# PhasedArrayTransmittor.net
KiCad netlist of a schematic drawn in EAGLE
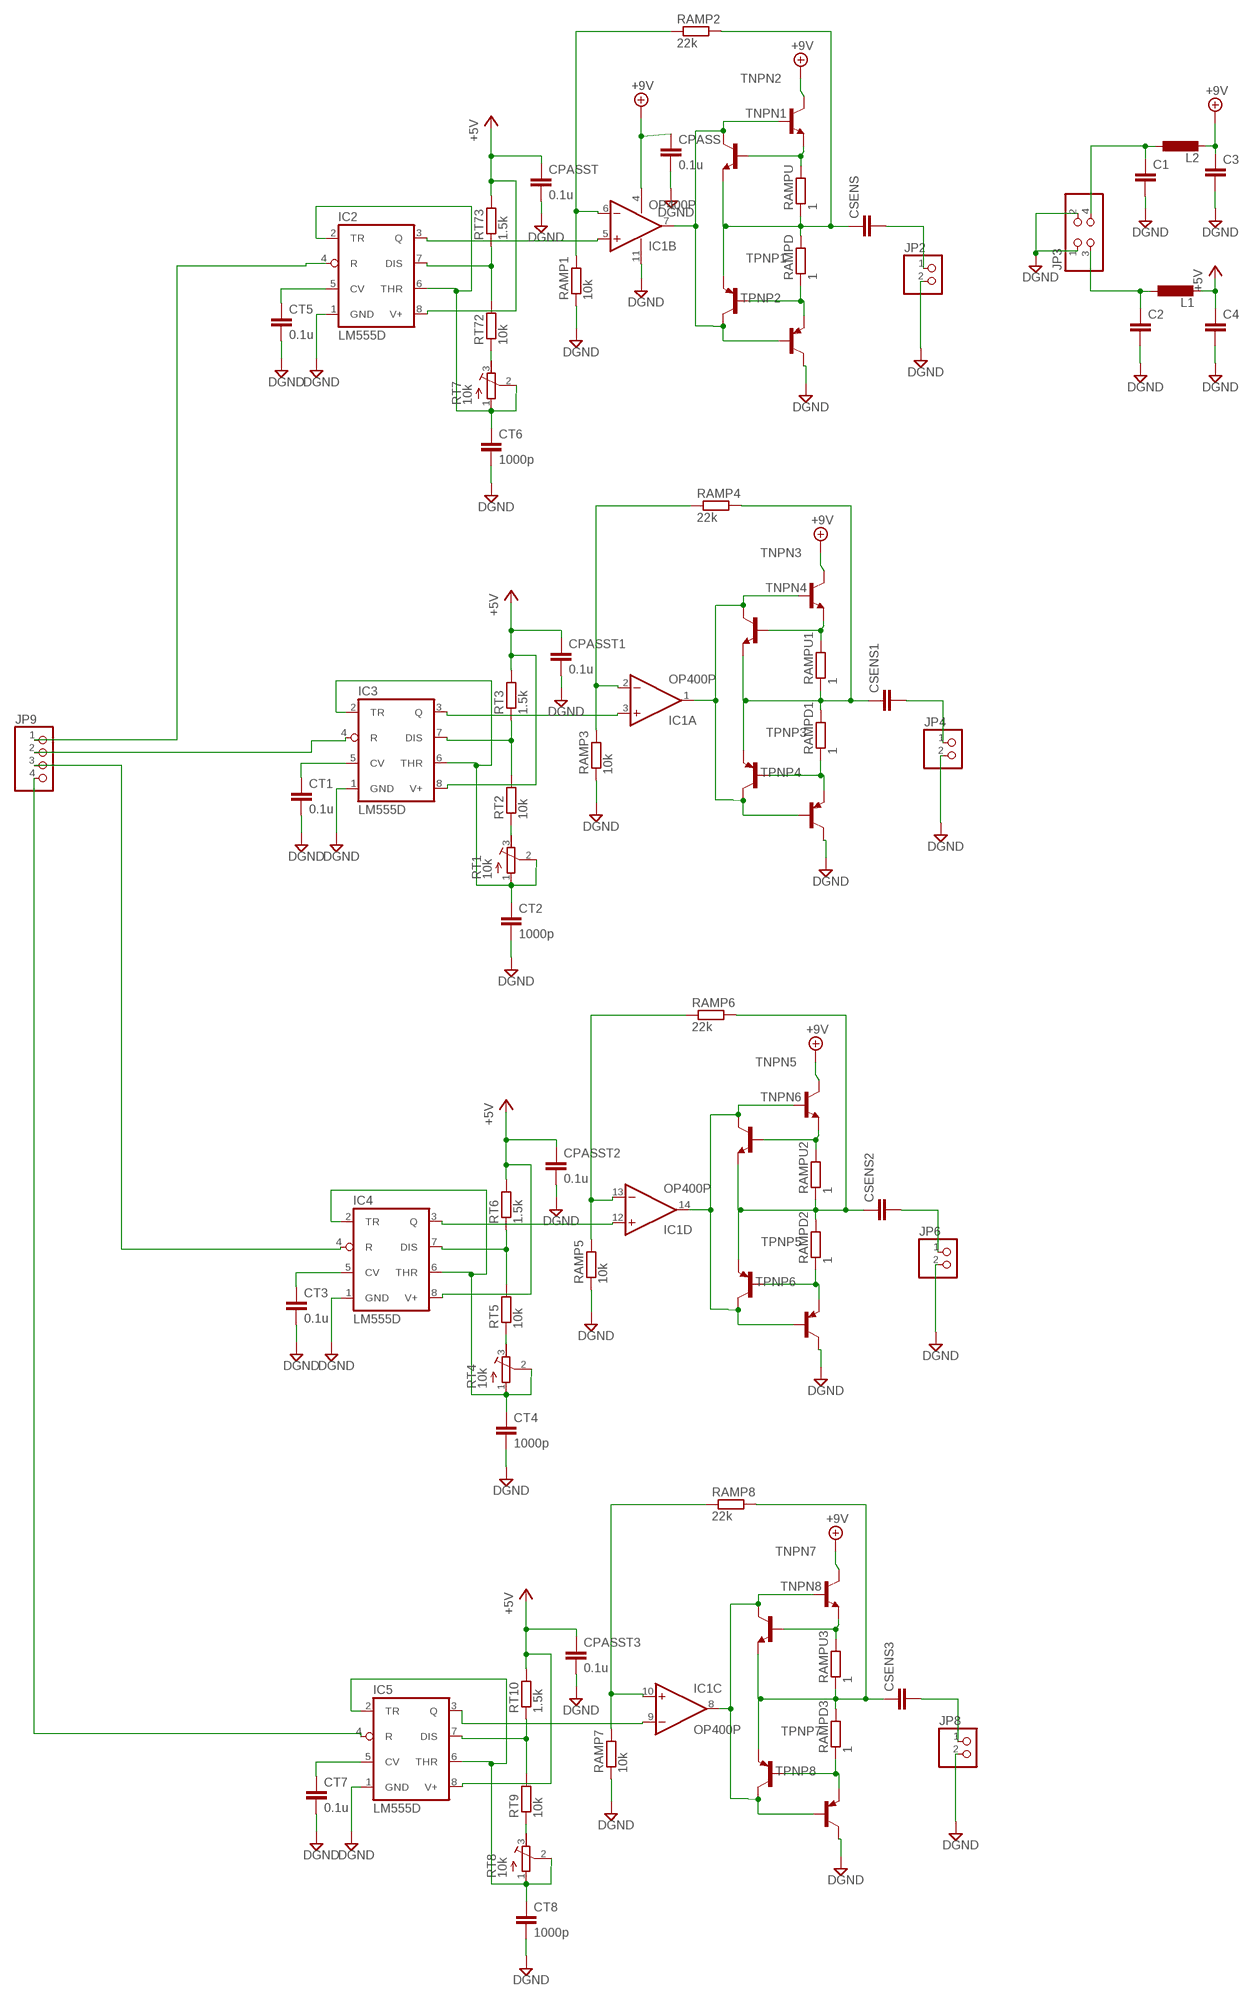
[diagram p0: schematic, sheet 1]

(export (version "E")
  (design (tool "Eeschema 10.0.6"))
  (components
    (comp (ref "C1")
      (value "C-EU025-024X044")
      (footprint "eagle-import:C025-024X044")
      (libsource (lib "eagle-import") (part "C-EU025-024X044"))
    )
    (comp (ref "C2")
      (value "C-EU025-024X044")
      (footprint "eagle-import:C025-024X044")
      (libsource (lib "eagle-import") (part "C-EU025-024X044"))
    )
    (comp (ref "C3")
      (value "C-EU025-024X044")
      (footprint "eagle-import:C025-024X044")
      (libsource (lib "eagle-import") (part "C-EU025-024X044"))
    )
    (comp (ref "C4")
      (value "C-EU025-024X044")
      (footprint "eagle-import:C025-024X044")
      (libsource (lib "eagle-import") (part "C-EU025-024X044"))
    )
    (comp (ref "CPASS")
      (value "0.1u")
      (footprint "eagle-import:C0603K")
      (libsource (lib "eagle-import") (part "C-EUC0603K"))
    )
    (comp (ref "CPASST")
      (value "0.1u")
      (footprint "eagle-import:C025-024X044")
      (libsource (lib "eagle-import") (part "C-EU025-024X044"))
    )
    (comp (ref "CPASST1")
      (value "0.1u")
      (footprint "eagle-import:C025-024X044")
      (libsource (lib "eagle-import") (part "C-EU025-024X044"))
    )
    (comp (ref "CPASST2")
      (value "0.1u")
      (footprint "eagle-import:C025-024X044")
      (libsource (lib "eagle-import") (part "C-EU025-024X044"))
    )
    (comp (ref "CPASST3")
      (value "0.1u")
      (footprint "eagle-import:C025-024X044")
      (libsource (lib "eagle-import") (part "C-EU025-024X044"))
    )
    (comp (ref "CSENS")
      (value "C-EUC0603K")
      (footprint "eagle-import:C0603K")
      (libsource (lib "eagle-import") (part "C-EUC0603K"))
    )
    (comp (ref "CSENS1")
      (value "C-EUC0603K")
      (footprint "eagle-import:C0603K")
      (libsource (lib "eagle-import") (part "C-EUC0603K"))
    )
    (comp (ref "CSENS2")
      (value "C-EUC0603K")
      (footprint "eagle-import:C0603K")
      (libsource (lib "eagle-import") (part "C-EUC0603K"))
    )
    (comp (ref "CSENS3")
      (value "C-EUC0603K")
      (footprint "eagle-import:C0603K")
      (libsource (lib "eagle-import") (part "C-EUC0603K"))
    )
    (comp (ref "CT1")
      (value "0.1u")
      (footprint "eagle-import:C025-024X044")
      (libsource (lib "eagle-import") (part "C-EU025-024X044"))
    )
    (comp (ref "CT2")
      (value "1000p")
      (footprint "eagle-import:C025-024X044")
      (libsource (lib "eagle-import") (part "C-EU025-024X044"))
    )
    (comp (ref "CT3")
      (value "0.1u")
      (footprint "eagle-import:C025-024X044")
      (libsource (lib "eagle-import") (part "C-EU025-024X044"))
    )
    (comp (ref "CT4")
      (value "1000p")
      (footprint "eagle-import:C025-024X044")
      (libsource (lib "eagle-import") (part "C-EU025-024X044"))
    )
    (comp (ref "CT5")
      (value "0.1u")
      (footprint "eagle-import:C025-024X044")
      (libsource (lib "eagle-import") (part "C-EU025-024X044"))
    )
    (comp (ref "CT6")
      (value "1000p")
      (footprint "eagle-import:C025-024X044")
      (libsource (lib "eagle-import") (part "C-EU025-024X044"))
    )
    (comp (ref "CT7")
      (value "0.1u")
      (footprint "eagle-import:C025-024X044")
      (libsource (lib "eagle-import") (part "C-EU025-024X044"))
    )
    (comp (ref "CT8")
      (value "1000p")
      (footprint "eagle-import:C025-024X044")
      (libsource (lib "eagle-import") (part "C-EU025-024X044"))
    )
    (comp (ref "IC1")
      (value "OP400P")
      (footprint "eagle-import:DIL14")
      (libsource (lib "eagle-import") (part "OP400P"))
    )
    (comp (ref "IC2")
      (value "LM555D")
      (footprint "eagle-import:SO08")
      (libsource (lib "eagle-import") (part "555DLM"))
    )
    (comp (ref "IC3")
      (value "LM555D")
      (footprint "eagle-import:SO08")
      (libsource (lib "eagle-import") (part "555DLM"))
    )
    (comp (ref "IC4")
      (value "LM555D")
      (footprint "eagle-import:SO08")
      (libsource (lib "eagle-import") (part "555DLM"))
    )
    (comp (ref "IC5")
      (value "LM555D")
      (footprint "eagle-import:SO08")
      (libsource (lib "eagle-import") (part "555DLM"))
    )
    (comp (ref "JP2")
      (value "PINHD-1X2")
      (footprint "eagle-import:1X02")
      (libsource (lib "eagle-import") (part "PINHD-1X2"))
    )
    (comp (ref "JP3")
      (value "PINHD-2X2")
      (footprint "eagle-import:2X02")
      (libsource (lib "eagle-import") (part "PINHD-2X2"))
    )
    (comp (ref "JP4")
      (value "PINHD-1X2")
      (footprint "eagle-import:1X02")
      (libsource (lib "eagle-import") (part "PINHD-1X2"))
    )
    (comp (ref "JP6")
      (value "PINHD-1X2")
      (footprint "eagle-import:1X02")
      (libsource (lib "eagle-import") (part "PINHD-1X2"))
    )
    (comp (ref "JP8")
      (value "PINHD-1X2")
      (footprint "eagle-import:1X02")
      (libsource (lib "eagle-import") (part "PINHD-1X2"))
    )
    (comp (ref "JP9")
      (value "PINHD-1X4")
      (footprint "eagle-import:1X04")
      (libsource (lib "eagle-import") (part "PINHD-1X4"))
    )
    (comp (ref "L1")
      (value "L-EU0207/7")
      (footprint "eagle-import:0207_7")
      (libsource (lib "eagle-import") (part "L-EU0207/7"))
    )
    (comp (ref "L2")
      (value "L-EU0207/7")
      (footprint "eagle-import:0207_7")
      (libsource (lib "eagle-import") (part "L-EU0207/7"))
    )
    (comp (ref "RAMP1")
      (value "10k")
      (footprint "eagle-import:R0603")
      (libsource (lib "eagle-import") (part "R-EU_R0603"))
    )
    (comp (ref "RAMP2")
      (value "22k")
      (footprint "eagle-import:R0603")
      (libsource (lib "eagle-import") (part "R-EU_R0603"))
    )
    (comp (ref "RAMP3")
      (value "10k")
      (footprint "eagle-import:R0603")
      (libsource (lib "eagle-import") (part "R-EU_R0603"))
    )
    (comp (ref "RAMP4")
      (value "22k")
      (footprint "eagle-import:R0603")
      (libsource (lib "eagle-import") (part "R-EU_R0603"))
    )
    (comp (ref "RAMP5")
      (value "10k")
      (footprint "eagle-import:R0603")
      (libsource (lib "eagle-import") (part "R-EU_R0603"))
    )
    (comp (ref "RAMP6")
      (value "22k")
      (footprint "eagle-import:R0603")
      (libsource (lib "eagle-import") (part "R-EU_R0603"))
    )
    (comp (ref "RAMP7")
      (value "10k")
      (footprint "eagle-import:R0603")
      (libsource (lib "eagle-import") (part "R-EU_R0603"))
    )
    (comp (ref "RAMP8")
      (value "22k")
      (footprint "eagle-import:R0603")
      (libsource (lib "eagle-import") (part "R-EU_R0603"))
    )
    (comp (ref "RAMPD")
      (value "1")
      (footprint "eagle-import:R0603")
      (libsource (lib "eagle-import") (part "R-EU_R0603"))
    )
    (comp (ref "RAMPD1")
      (value "1")
      (footprint "eagle-import:R0603")
      (libsource (lib "eagle-import") (part "R-EU_R0603"))
    )
    (comp (ref "RAMPD2")
      (value "1")
      (footprint "eagle-import:R0603")
      (libsource (lib "eagle-import") (part "R-EU_R0603"))
    )
    (comp (ref "RAMPD3")
      (value "1")
      (footprint "eagle-import:R0603")
      (libsource (lib "eagle-import") (part "R-EU_R0603"))
    )
    (comp (ref "RAMPU")
      (value "1")
      (footprint "eagle-import:R0603")
      (libsource (lib "eagle-import") (part "R-EU_R0603"))
    )
    (comp (ref "RAMPU1")
      (value "1")
      (footprint "eagle-import:R0603")
      (libsource (lib "eagle-import") (part "R-EU_R0603"))
    )
    (comp (ref "RAMPU2")
      (value "1")
      (footprint "eagle-import:R0603")
      (libsource (lib "eagle-import") (part "R-EU_R0603"))
    )
    (comp (ref "RAMPU3")
      (value "1")
      (footprint "eagle-import:R0603")
      (libsource (lib "eagle-import") (part "R-EU_R0603"))
    )
    (comp (ref "RT1")
      (value "10k")
      (footprint "eagle-import:RTRIM74W")
      (libsource (lib "eagle-import") (part "R-TRIMM74W"))
    )
    (comp (ref "RT2")
      (value "10k")
      (footprint "eagle-import:R0603")
      (libsource (lib "eagle-import") (part "R-EU_R0603"))
    )
    (comp (ref "RT3")
      (value "1.5k")
      (footprint "eagle-import:R0603")
      (libsource (lib "eagle-import") (part "R-EU_R0603"))
    )
    (comp (ref "RT4")
      (value "10k")
      (footprint "eagle-import:RTRIM74W")
      (libsource (lib "eagle-import") (part "R-TRIMM74W"))
    )
    (comp (ref "RT5")
      (value "10k")
      (footprint "eagle-import:R0603")
      (libsource (lib "eagle-import") (part "R-EU_R0603"))
    )
    (comp (ref "RT6")
      (value "1.5k")
      (footprint "eagle-import:R0603")
      (libsource (lib "eagle-import") (part "R-EU_R0603"))
    )
    (comp (ref "RT7")
      (value "10k")
      (footprint "eagle-import:RTRIM74W")
      (libsource (lib "eagle-import") (part "R-TRIMM74W"))
    )
    (comp (ref "RT8")
      (value "10k")
      (footprint "eagle-import:RTRIM74W")
      (libsource (lib "eagle-import") (part "R-TRIMM74W"))
    )
    (comp (ref "RT9")
      (value "10k")
      (footprint "eagle-import:R0603")
      (libsource (lib "eagle-import") (part "R-EU_R0603"))
    )
    (comp (ref "RT10")
      (value "1.5k")
      (footprint "eagle-import:R0603")
      (libsource (lib "eagle-import") (part "R-EU_R0603"))
    )
    (comp (ref "RT72")
      (value "10k")
      (footprint "eagle-import:R0603")
      (libsource (lib "eagle-import") (part "R-EU_R0603"))
    )
    (comp (ref "RT73")
      (value "1.5k")
      (footprint "eagle-import:R0603")
      (libsource (lib "eagle-import") (part "R-EU_R0603"))
    )
    (comp (ref "TNPN1")
      (value "BC817-16-NPN-SOT23-BEC")
      (footprint "eagle-import:SOT23-BEC")
      (libsource (lib "eagle-import") (part "-NPN-SOT23-BECBC817-16"))
    )
    (comp (ref "TNPN2")
      (value "BC817-16-NPN-SOT23-BEC")
      (footprint "eagle-import:SOT23-BEC")
      (libsource (lib "eagle-import") (part "-NPN-SOT23-BECBC817-16"))
    )
    (comp (ref "TNPN3")
      (value "BC817-16-NPN-SOT23-BEC")
      (footprint "eagle-import:SOT23-BEC")
      (libsource (lib "eagle-import") (part "-NPN-SOT23-BECBC817-16"))
    )
    (comp (ref "TNPN4")
      (value "BC817-16-NPN-SOT23-BEC")
      (footprint "eagle-import:SOT23-BEC")
      (libsource (lib "eagle-import") (part "-NPN-SOT23-BECBC817-16"))
    )
    (comp (ref "TNPN5")
      (value "BC817-16-NPN-SOT23-BEC")
      (footprint "eagle-import:SOT23-BEC")
      (libsource (lib "eagle-import") (part "-NPN-SOT23-BECBC817-16"))
    )
    (comp (ref "TNPN6")
      (value "BC817-16-NPN-SOT23-BEC")
      (footprint "eagle-import:SOT23-BEC")
      (libsource (lib "eagle-import") (part "-NPN-SOT23-BECBC817-16"))
    )
    (comp (ref "TNPN7")
      (value "BC817-16-NPN-SOT23-BEC")
      (footprint "eagle-import:SOT23-BEC")
      (libsource (lib "eagle-import") (part "-NPN-SOT23-BECBC817-16"))
    )
    (comp (ref "TNPN8")
      (value "BC817-16-NPN-SOT23-BEC")
      (footprint "eagle-import:SOT23-BEC")
      (libsource (lib "eagle-import") (part "-NPN-SOT23-BECBC817-16"))
    )
    (comp (ref "TPNP1")
      (value "BC807-16-PNP-SOT23-BEC")
      (footprint "eagle-import:SOT23-BEC")
      (libsource (lib "eagle-import") (part "-PNP-SOT23-BECBC807-16"))
    )
    (comp (ref "TPNP2")
      (value "BC807-16-PNP-SOT23-BEC")
      (footprint "eagle-import:SOT23-BEC")
      (libsource (lib "eagle-import") (part "-PNP-SOT23-BECBC807-16"))
    )
    (comp (ref "TPNP3")
      (value "BC807-16-PNP-SOT23-BEC")
      (footprint "eagle-import:SOT23-BEC")
      (libsource (lib "eagle-import") (part "-PNP-SOT23-BECBC807-16"))
    )
    (comp (ref "TPNP4")
      (value "BC807-16-PNP-SOT23-BEC")
      (footprint "eagle-import:SOT23-BEC")
      (libsource (lib "eagle-import") (part "-PNP-SOT23-BECBC807-16"))
    )
    (comp (ref "TPNP5")
      (value "BC807-16-PNP-SOT23-BEC")
      (footprint "eagle-import:SOT23-BEC")
      (libsource (lib "eagle-import") (part "-PNP-SOT23-BECBC807-16"))
    )
    (comp (ref "TPNP6")
      (value "BC807-16-PNP-SOT23-BEC")
      (footprint "eagle-import:SOT23-BEC")
      (libsource (lib "eagle-import") (part "-PNP-SOT23-BECBC807-16"))
    )
    (comp (ref "TPNP7")
      (value "BC807-16-PNP-SOT23-BEC")
      (footprint "eagle-import:SOT23-BEC")
      (libsource (lib "eagle-import") (part "-PNP-SOT23-BECBC807-16"))
    )
    (comp (ref "TPNP8")
      (value "BC807-16-PNP-SOT23-BEC")
      (footprint "eagle-import:SOT23-BEC")
      (libsource (lib "eagle-import") (part "-PNP-SOT23-BECBC807-16"))
    )
  )
  (nets
    (net (code "1") (name "+5V") (class "Default")
      (node (ref "C4") (pin "1") (pinfunction "1_1") (pintype "passive"))
      (node (ref "CPASST") (pin "1") (pinfunction "1_1") (pintype "passive"))
      (node (ref "CPASST1") (pin "1") (pinfunction "1_1") (pintype "passive"))
      (node (ref "CPASST2") (pin "1") (pinfunction "1_1") (pintype "passive"))
      (node (ref "CPASST3") (pin "1") (pinfunction "1_1") (pintype "passive"))
      (node (ref "IC2") (pin "8") (pinfunction "V+_8") (pintype "power_in"))
      (node (ref "IC3") (pin "8") (pinfunction "V+_8") (pintype "power_in"))
      (node (ref "IC4") (pin "8") (pinfunction "V+_8") (pintype "power_in"))
      (node (ref "IC5") (pin "8") (pinfunction "V+_8") (pintype "power_in"))
      (node (ref "L1") (pin "2") (pinfunction "2_2") (pintype "passive"))
      (node (ref "RT10") (pin "2") (pinfunction "2_2") (pintype "passive"))
      (node (ref "RT3") (pin "2") (pinfunction "2_2") (pintype "passive"))
      (node (ref "RT6") (pin "2") (pinfunction "2_2") (pintype "passive"))
      (node (ref "RT73") (pin "2") (pinfunction "2_2") (pintype "passive"))
    )
    (net (code "2") (name "+9V") (class "Default")
      (node (ref "C3") (pin "1") (pinfunction "1_1") (pintype "passive"))
      (node (ref "CPASS") (pin "1") (pinfunction "1_1") (pintype "passive"))
      (node (ref "IC1") (pin "4") (pinfunction "V+_4") (pintype "power_in"))
      (node (ref "L2") (pin "2") (pinfunction "2_2") (pintype "passive"))
      (node (ref "TNPN2") (pin "C") (pinfunction "C_C") (pintype "passive"))
      (node (ref "TNPN3") (pin "C") (pinfunction "C_C") (pintype "passive"))
      (node (ref "TNPN5") (pin "C") (pinfunction "C_C") (pintype "passive"))
      (node (ref "TNPN7") (pin "C") (pinfunction "C_C") (pintype "passive"))
    )
    (net (code "3") (name "DGND") (class "Default")
      (node (ref "C1") (pin "2") (pinfunction "2_2") (pintype "passive"))
      (node (ref "C2") (pin "2") (pinfunction "2_2") (pintype "passive"))
      (node (ref "C3") (pin "2") (pinfunction "2_2") (pintype "passive"))
      (node (ref "C4") (pin "2") (pinfunction "2_2") (pintype "passive"))
      (node (ref "CPASS") (pin "2") (pinfunction "2_2") (pintype "passive"))
      (node (ref "CPASST") (pin "2") (pinfunction "2_2") (pintype "passive"))
      (node (ref "CPASST1") (pin "2") (pinfunction "2_2") (pintype "passive"))
      (node (ref "CPASST2") (pin "2") (pinfunction "2_2") (pintype "passive"))
      (node (ref "CPASST3") (pin "2") (pinfunction "2_2") (pintype "passive"))
      (node (ref "CT1") (pin "2") (pinfunction "2_2") (pintype "passive"))
      (node (ref "CT2") (pin "2") (pinfunction "2_2") (pintype "passive"))
      (node (ref "CT3") (pin "2") (pinfunction "2_2") (pintype "passive"))
      (node (ref "CT4") (pin "2") (pinfunction "2_2") (pintype "passive"))
      (node (ref "CT5") (pin "2") (pinfunction "2_2") (pintype "passive"))
      (node (ref "CT6") (pin "2") (pinfunction "2_2") (pintype "passive"))
      (node (ref "CT7") (pin "2") (pinfunction "2_2") (pintype "passive"))
      (node (ref "CT8") (pin "2") (pinfunction "2_2") (pintype "passive"))
      (node (ref "IC1") (pin "11") (pinfunction "V-_11") (pintype "power_in"))
      (node (ref "IC2") (pin "1") (pinfunction "GND_1") (pintype "power_in"))
      (node (ref "IC3") (pin "1") (pinfunction "GND_1") (pintype "power_in"))
      (node (ref "IC4") (pin "1") (pinfunction "GND_1") (pintype "power_in"))
      (node (ref "IC5") (pin "1") (pinfunction "GND_1") (pintype "power_in"))
      (node (ref "JP2") (pin "2") (pinfunction "2_2") (pintype "passive"))
      (node (ref "JP3") (pin "1") (pinfunction "1_1") (pintype "passive"))
      (node (ref "JP3") (pin "2") (pinfunction "2_2") (pintype "passive"))
      (node (ref "JP4") (pin "2") (pinfunction "2_2") (pintype "passive"))
      (node (ref "JP6") (pin "2") (pinfunction "2_2") (pintype "passive"))
      (node (ref "JP8") (pin "2") (pinfunction "2_2") (pintype "passive"))
      (node (ref "RAMP1") (pin "1") (pinfunction "1_1") (pintype "passive"))
      (node (ref "RAMP3") (pin "1") (pinfunction "1_1") (pintype "passive"))
      (node (ref "RAMP5") (pin "1") (pinfunction "1_1") (pintype "passive"))
      (node (ref "RAMP7") (pin "1") (pinfunction "1_1") (pintype "passive"))
      (node (ref "TPNP2") (pin "C") (pinfunction "C_C") (pintype "passive"))
      (node (ref "TPNP4") (pin "C") (pinfunction "C_C") (pintype "passive"))
      (node (ref "TPNP6") (pin "C") (pinfunction "C_C") (pintype "passive"))
      (node (ref "TPNP8") (pin "C") (pinfunction "C_C") (pintype "passive"))
    )
    (net (code "4") (name "Net-(C1-Pad1)") (class "Default")
      (node (ref "C1") (pin "1") (pinfunction "1_1") (pintype "passive"))
      (node (ref "JP3") (pin "4") (pinfunction "4_4") (pintype "passive"))
      (node (ref "L2") (pin "1") (pinfunction "1_1") (pintype "passive"))
    )
    (net (code "5") (name "Net-(C2-Pad1)") (class "Default")
      (node (ref "C2") (pin "1") (pinfunction "1_1") (pintype "passive"))
      (node (ref "JP3") (pin "3") (pinfunction "3_3") (pintype "passive"))
      (node (ref "L1") (pin "1") (pinfunction "1_1") (pintype "passive"))
    )
    (net (code "6") (name "Net-(CSENS-Pad1)") (class "Default")
      (node (ref "CSENS") (pin "1") (pinfunction "1_1") (pintype "passive"))
      (node (ref "RAMP2") (pin "2") (pinfunction "2_2") (pintype "passive"))
      (node (ref "RAMPD") (pin "2") (pinfunction "2_2") (pintype "passive"))
      (node (ref "RAMPU") (pin "1") (pinfunction "1_1") (pintype "passive"))
      (node (ref "TNPN1") (pin "E") (pinfunction "E_E") (pintype "passive"))
      (node (ref "TPNP1") (pin "E") (pinfunction "E_E") (pintype "passive"))
    )
    (net (code "7") (name "Net-(CSENS-Pad2)") (class "Default")
      (node (ref "CSENS") (pin "2") (pinfunction "2_2") (pintype "passive"))
      (node (ref "JP2") (pin "1") (pinfunction "1_1") (pintype "passive"))
    )
    (net (code "8") (name "Net-(CSENS1-Pad1)") (class "Default")
      (node (ref "CSENS1") (pin "1") (pinfunction "1_1") (pintype "passive"))
      (node (ref "RAMP4") (pin "2") (pinfunction "2_2") (pintype "passive"))
      (node (ref "RAMPD1") (pin "2") (pinfunction "2_2") (pintype "passive"))
      (node (ref "RAMPU1") (pin "1") (pinfunction "1_1") (pintype "passive"))
      (node (ref "TNPN4") (pin "E") (pinfunction "E_E") (pintype "passive"))
      (node (ref "TPNP3") (pin "E") (pinfunction "E_E") (pintype "passive"))
    )
    (net (code "9") (name "Net-(CSENS1-Pad2)") (class "Default")
      (node (ref "CSENS1") (pin "2") (pinfunction "2_2") (pintype "passive"))
      (node (ref "JP4") (pin "1") (pinfunction "1_1") (pintype "passive"))
    )
    (net (code "10") (name "Net-(CSENS2-Pad1)") (class "Default")
      (node (ref "CSENS2") (pin "1") (pinfunction "1_1") (pintype "passive"))
      (node (ref "RAMP6") (pin "2") (pinfunction "2_2") (pintype "passive"))
      (node (ref "RAMPD2") (pin "2") (pinfunction "2_2") (pintype "passive"))
      (node (ref "RAMPU2") (pin "1") (pinfunction "1_1") (pintype "passive"))
      (node (ref "TNPN6") (pin "E") (pinfunction "E_E") (pintype "passive"))
      (node (ref "TPNP5") (pin "E") (pinfunction "E_E") (pintype "passive"))
    )
    (net (code "11") (name "Net-(CSENS2-Pad2)") (class "Default")
      (node (ref "CSENS2") (pin "2") (pinfunction "2_2") (pintype "passive"))
      (node (ref "JP6") (pin "1") (pinfunction "1_1") (pintype "passive"))
    )
    (net (code "12") (name "Net-(CSENS3-Pad1)") (class "Default")
      (node (ref "CSENS3") (pin "1") (pinfunction "1_1") (pintype "passive"))
      (node (ref "RAMP8") (pin "2") (pinfunction "2_2") (pintype "passive"))
      (node (ref "RAMPD3") (pin "2") (pinfunction "2_2") (pintype "passive"))
      (node (ref "RAMPU3") (pin "1") (pinfunction "1_1") (pintype "passive"))
      (node (ref "TNPN8") (pin "E") (pinfunction "E_E") (pintype "passive"))
      (node (ref "TPNP7") (pin "E") (pinfunction "E_E") (pintype "passive"))
    )
    (net (code "13") (name "Net-(CSENS3-Pad2)") (class "Default")
      (node (ref "CSENS3") (pin "2") (pinfunction "2_2") (pintype "passive"))
      (node (ref "JP8") (pin "1") (pinfunction "1_1") (pintype "passive"))
    )
    (net (code "14") (name "Net-(IC1A-+IN)") (class "Default")
      (node (ref "IC1") (pin "3") (pinfunction "+IN_3") (pintype "input"))
      (node (ref "IC3") (pin "3") (pinfunction "Q_3") (pintype "output"))
    )
    (net (code "15") (name "Net-(IC1A--IN)") (class "Default")
      (node (ref "IC1") (pin "2") (pinfunction "-IN_2") (pintype "input"))
      (node (ref "RAMP3") (pin "2") (pinfunction "2_2") (pintype "passive"))
      (node (ref "RAMP4") (pin "1") (pinfunction "1_1") (pintype "passive"))
    )
    (net (code "16") (name "Net-(IC1A-OUT)") (class "Default")
      (node (ref "IC1") (pin "1") (pinfunction "OUT_1") (pintype "output"))
      (node (ref "TNPN3") (pin "B") (pinfunction "B_B") (pintype "passive"))
      (node (ref "TNPN4") (pin "C") (pinfunction "C_C") (pintype "passive"))
      (node (ref "TPNP3") (pin "C") (pinfunction "C_C") (pintype "passive"))
      (node (ref "TPNP4") (pin "B") (pinfunction "B_B") (pintype "passive"))
    )
    (net (code "17") (name "Net-(IC1B-+IN)") (class "Default")
      (node (ref "IC1") (pin "5") (pinfunction "+IN_5") (pintype "input"))
      (node (ref "IC2") (pin "3") (pinfunction "Q_3") (pintype "output"))
    )
    (net (code "18") (name "Net-(IC1B--IN)") (class "Default")
      (node (ref "IC1") (pin "6") (pinfunction "-IN_6") (pintype "input"))
      (node (ref "RAMP1") (pin "2") (pinfunction "2_2") (pintype "passive"))
      (node (ref "RAMP2") (pin "1") (pinfunction "1_1") (pintype "passive"))
    )
    (net (code "19") (name "Net-(IC1B-OUT)") (class "Default")
      (node (ref "IC1") (pin "7") (pinfunction "OUT_7") (pintype "output"))
      (node (ref "TNPN1") (pin "C") (pinfunction "C_C") (pintype "passive"))
      (node (ref "TNPN2") (pin "B") (pinfunction "B_B") (pintype "passive"))
      (node (ref "TPNP1") (pin "C") (pinfunction "C_C") (pintype "passive"))
      (node (ref "TPNP2") (pin "B") (pinfunction "B_B") (pintype "passive"))
    )
    (net (code "20") (name "Net-(IC1C-+IN)") (class "Default")
      (node (ref "IC1") (pin "10") (pinfunction "+IN_10") (pintype "input"))
      (node (ref "RAMP7") (pin "2") (pinfunction "2_2") (pintype "passive"))
      (node (ref "RAMP8") (pin "1") (pinfunction "1_1") (pintype "passive"))
    )
    (net (code "21") (name "Net-(IC1C--IN)") (class "Default")
      (node (ref "IC1") (pin "9") (pinfunction "-IN_9") (pintype "input"))
      (node (ref "IC5") (pin "3") (pinfunction "Q_3") (pintype "output"))
    )
    (net (code "22") (name "Net-(IC1C-OUT)") (class "Default")
      (node (ref "IC1") (pin "8") (pinfunction "OUT_8") (pintype "output"))
      (node (ref "TNPN7") (pin "B") (pinfunction "B_B") (pintype "passive"))
      (node (ref "TNPN8") (pin "C") (pinfunction "C_C") (pintype "passive"))
      (node (ref "TPNP7") (pin "C") (pinfunction "C_C") (pintype "passive"))
      (node (ref "TPNP8") (pin "B") (pinfunction "B_B") (pintype "passive"))
    )
    (net (code "23") (name "Net-(IC1D-+IN)") (class "Default")
      (node (ref "IC1") (pin "12") (pinfunction "+IN_12") (pintype "input"))
      (node (ref "IC4") (pin "3") (pinfunction "Q_3") (pintype "output"))
    )
    (net (code "24") (name "Net-(IC1D--IN)") (class "Default")
      (node (ref "IC1") (pin "13") (pinfunction "-IN_13") (pintype "input"))
      (node (ref "RAMP5") (pin "2") (pinfunction "2_2") (pintype "passive"))
      (node (ref "RAMP6") (pin "1") (pinfunction "1_1") (pintype "passive"))
    )
    (net (code "25") (name "Net-(IC1D-OUT)") (class "Default")
      (node (ref "IC1") (pin "14") (pinfunction "OUT_14") (pintype "output"))
      (node (ref "TNPN5") (pin "B") (pinfunction "B_B") (pintype "passive"))
      (node (ref "TNPN6") (pin "C") (pinfunction "C_C") (pintype "passive"))
      (node (ref "TPNP5") (pin "C") (pinfunction "C_C") (pintype "passive"))
      (node (ref "TPNP6") (pin "B") (pinfunction "B_B") (pintype "passive"))
    )
    (net (code "26") (name "Net-(IC2-CV)") (class "Default")
      (node (ref "CT5") (pin "1") (pinfunction "1_1") (pintype "passive"))
      (node (ref "IC2") (pin "5") (pinfunction "CV_5") (pintype "input"))
    )
    (net (code "27") (name "Net-(IC2-DIS)") (class "Default")
      (node (ref "IC2") (pin "7") (pinfunction "DIS_7") (pintype "input"))
      (node (ref "RT72") (pin "2") (pinfunction "2_2") (pintype "passive"))
      (node (ref "RT73") (pin "1") (pinfunction "1_1") (pintype "passive"))
    )
    (net (code "28") (name "Net-(IC2-R)") (class "Default")
      (node (ref "IC2") (pin "4") (pinfunction "R_4") (pintype "input"))
      (node (ref "JP9") (pin "1") (pinfunction "1_1") (pintype "passive"))
    )
    (net (code "29") (name "Net-(IC2-THR)") (class "Default")
      (node (ref "CT6") (pin "1") (pinfunction "1_1") (pintype "passive"))
      (node (ref "IC2") (pin "2") (pinfunction "TR_2") (pintype "input"))
      (node (ref "IC2") (pin "6") (pinfunction "THR_6") (pintype "input"))
      (node (ref "RT7") (pin "1") (pinfunction "A_1") (pintype "passive"))
      (node (ref "RT7") (pin "2") (pinfunction "S_2") (pintype "passive"))
    )
    (net (code "30") (name "Net-(IC3-CV)") (class "Default")
      (node (ref "CT1") (pin "1") (pinfunction "1_1") (pintype "passive"))
      (node (ref "IC3") (pin "5") (pinfunction "CV_5") (pintype "input"))
    )
    (net (code "31") (name "Net-(IC3-DIS)") (class "Default")
      (node (ref "IC3") (pin "7") (pinfunction "DIS_7") (pintype "input"))
      (node (ref "RT2") (pin "2") (pinfunction "2_2") (pintype "passive"))
      (node (ref "RT3") (pin "1") (pinfunction "1_1") (pintype "passive"))
    )
    (net (code "32") (name "Net-(IC3-R)") (class "Default")
      (node (ref "IC3") (pin "4") (pinfunction "R_4") (pintype "input"))
      (node (ref "JP9") (pin "2") (pinfunction "2_2") (pintype "passive"))
    )
    (net (code "33") (name "Net-(IC3-THR)") (class "Default")
      (node (ref "CT2") (pin "1") (pinfunction "1_1") (pintype "passive"))
      (node (ref "IC3") (pin "2") (pinfunction "TR_2") (pintype "input"))
      (node (ref "IC3") (pin "6") (pinfunction "THR_6") (pintype "input"))
      (node (ref "RT1") (pin "1") (pinfunction "A_1") (pintype "passive"))
      (node (ref "RT1") (pin "2") (pinfunction "S_2") (pintype "passive"))
    )
    (net (code "34") (name "Net-(IC4-CV)") (class "Default")
      (node (ref "CT3") (pin "1") (pinfunction "1_1") (pintype "passive"))
      (node (ref "IC4") (pin "5") (pinfunction "CV_5") (pintype "input"))
    )
    (net (code "35") (name "Net-(IC4-DIS)") (class "Default")
      (node (ref "IC4") (pin "7") (pinfunction "DIS_7") (pintype "input"))
      (node (ref "RT5") (pin "2") (pinfunction "2_2") (pintype "passive"))
      (node (ref "RT6") (pin "1") (pinfunction "1_1") (pintype "passive"))
    )
    (net (code "36") (name "Net-(IC4-R)") (class "Default")
      (node (ref "IC4") (pin "4") (pinfunction "R_4") (pintype "input"))
      (node (ref "JP9") (pin "3") (pinfunction "3_3") (pintype "passive"))
    )
    (net (code "37") (name "Net-(IC4-THR)") (class "Default")
      (node (ref "CT4") (pin "1") (pinfunction "1_1") (pintype "passive"))
      (node (ref "IC4") (pin "2") (pinfunction "TR_2") (pintype "input"))
      (node (ref "IC4") (pin "6") (pinfunction "THR_6") (pintype "input"))
      (node (ref "RT4") (pin "1") (pinfunction "A_1") (pintype "passive"))
      (node (ref "RT4") (pin "2") (pinfunction "S_2") (pintype "passive"))
    )
    (net (code "38") (name "Net-(IC5-CV)") (class "Default")
      (node (ref "CT7") (pin "1") (pinfunction "1_1") (pintype "passive"))
      (node (ref "IC5") (pin "5") (pinfunction "CV_5") (pintype "input"))
    )
    (net (code "39") (name "Net-(IC5-DIS)") (class "Default")
      (node (ref "IC5") (pin "7") (pinfunction "DIS_7") (pintype "input"))
      (node (ref "RT10") (pin "1") (pinfunction "1_1") (pintype "passive"))
      (node (ref "RT9") (pin "2") (pinfunction "2_2") (pintype "passive"))
    )
    (net (code "40") (name "Net-(IC5-R)") (class "Default")
      (node (ref "IC5") (pin "4") (pinfunction "R_4") (pintype "input"))
      (node (ref "JP9") (pin "4") (pinfunction "4_4") (pintype "passive"))
    )
    (net (code "41") (name "Net-(IC5-THR)") (class "Default")
      (node (ref "CT8") (pin "1") (pinfunction "1_1") (pintype "passive"))
      (node (ref "IC5") (pin "2") (pinfunction "TR_2") (pintype "input"))
      (node (ref "IC5") (pin "6") (pinfunction "THR_6") (pintype "input"))
      (node (ref "RT8") (pin "1") (pinfunction "A_1") (pintype "passive"))
      (node (ref "RT8") (pin "2") (pinfunction "S_2") (pintype "passive"))
    )
    (net (code "42") (name "Net-(RAMPD-Pad1)") (class "Default")
      (node (ref "RAMPD") (pin "1") (pinfunction "1_1") (pintype "passive"))
      (node (ref "TPNP1") (pin "B") (pinfunction "B_B") (pintype "passive"))
      (node (ref "TPNP2") (pin "E") (pinfunction "E_E") (pintype "passive"))
    )
    (net (code "43") (name "Net-(RAMPD1-Pad1)") (class "Default")
      (node (ref "RAMPD1") (pin "1") (pinfunction "1_1") (pintype "passive"))
      (node (ref "TPNP3") (pin "B") (pinfunction "B_B") (pintype "passive"))
      (node (ref "TPNP4") (pin "E") (pinfunction "E_E") (pintype "passive"))
    )
    (net (code "44") (name "Net-(RAMPD2-Pad1)") (class "Default")
      (node (ref "RAMPD2") (pin "1") (pinfunction "1_1") (pintype "passive"))
      (node (ref "TPNP5") (pin "B") (pinfunction "B_B") (pintype "passive"))
      (node (ref "TPNP6") (pin "E") (pinfunction "E_E") (pintype "passive"))
    )
    (net (code "45") (name "Net-(RAMPD3-Pad1)") (class "Default")
      (node (ref "RAMPD3") (pin "1") (pinfunction "1_1") (pintype "passive"))
      (node (ref "TPNP7") (pin "B") (pinfunction "B_B") (pintype "passive"))
      (node (ref "TPNP8") (pin "E") (pinfunction "E_E") (pintype "passive"))
    )
    (net (code "46") (name "Net-(RAMPU-Pad2)") (class "Default")
      (node (ref "RAMPU") (pin "2") (pinfunction "2_2") (pintype "passive"))
      (node (ref "TNPN1") (pin "B") (pinfunction "B_B") (pintype "passive"))
      (node (ref "TNPN2") (pin "E") (pinfunction "E_E") (pintype "passive"))
    )
    (net (code "47") (name "Net-(RAMPU1-Pad2)") (class "Default")
      (node (ref "RAMPU1") (pin "2") (pinfunction "2_2") (pintype "passive"))
      (node (ref "TNPN3") (pin "E") (pinfunction "E_E") (pintype "passive"))
      (node (ref "TNPN4") (pin "B") (pinfunction "B_B") (pintype "passive"))
    )
    (net (code "48") (name "Net-(RAMPU2-Pad2)") (class "Default")
      (node (ref "RAMPU2") (pin "2") (pinfunction "2_2") (pintype "passive"))
      (node (ref "TNPN5") (pin "E") (pinfunction "E_E") (pintype "passive"))
      (node (ref "TNPN6") (pin "B") (pinfunction "B_B") (pintype "passive"))
    )
    (net (code "49") (name "Net-(RAMPU3-Pad2)") (class "Default")
      (node (ref "RAMPU3") (pin "2") (pinfunction "2_2") (pintype "passive"))
      (node (ref "TNPN7") (pin "E") (pinfunction "E_E") (pintype "passive"))
      (node (ref "TNPN8") (pin "B") (pinfunction "B_B") (pintype "passive"))
    )
    (net (code "50") (name "Net-(RT1-E)") (class "Default")
      (node (ref "RT1") (pin "3") (pinfunction "E_3") (pintype "passive"))
      (node (ref "RT2") (pin "1") (pinfunction "1_1") (pintype "passive"))
    )
    (net (code "51") (name "Net-(RT4-E)") (class "Default")
      (node (ref "RT4") (pin "3") (pinfunction "E_3") (pintype "passive"))
      (node (ref "RT5") (pin "1") (pinfunction "1_1") (pintype "passive"))
    )
    (net (code "52") (name "Net-(RT7-E)") (class "Default")
      (node (ref "RT7") (pin "3") (pinfunction "E_3") (pintype "passive"))
      (node (ref "RT72") (pin "1") (pinfunction "1_1") (pintype "passive"))
    )
    (net (code "53") (name "Net-(RT8-E)") (class "Default")
      (node (ref "RT8") (pin "3") (pinfunction "E_3") (pintype "passive"))
      (node (ref "RT9") (pin "1") (pinfunction "1_1") (pintype "passive"))
    )
  )
)
